# SCHEMATIC_V2.net
KiCad netlist of a schematic drawn in EAGLE
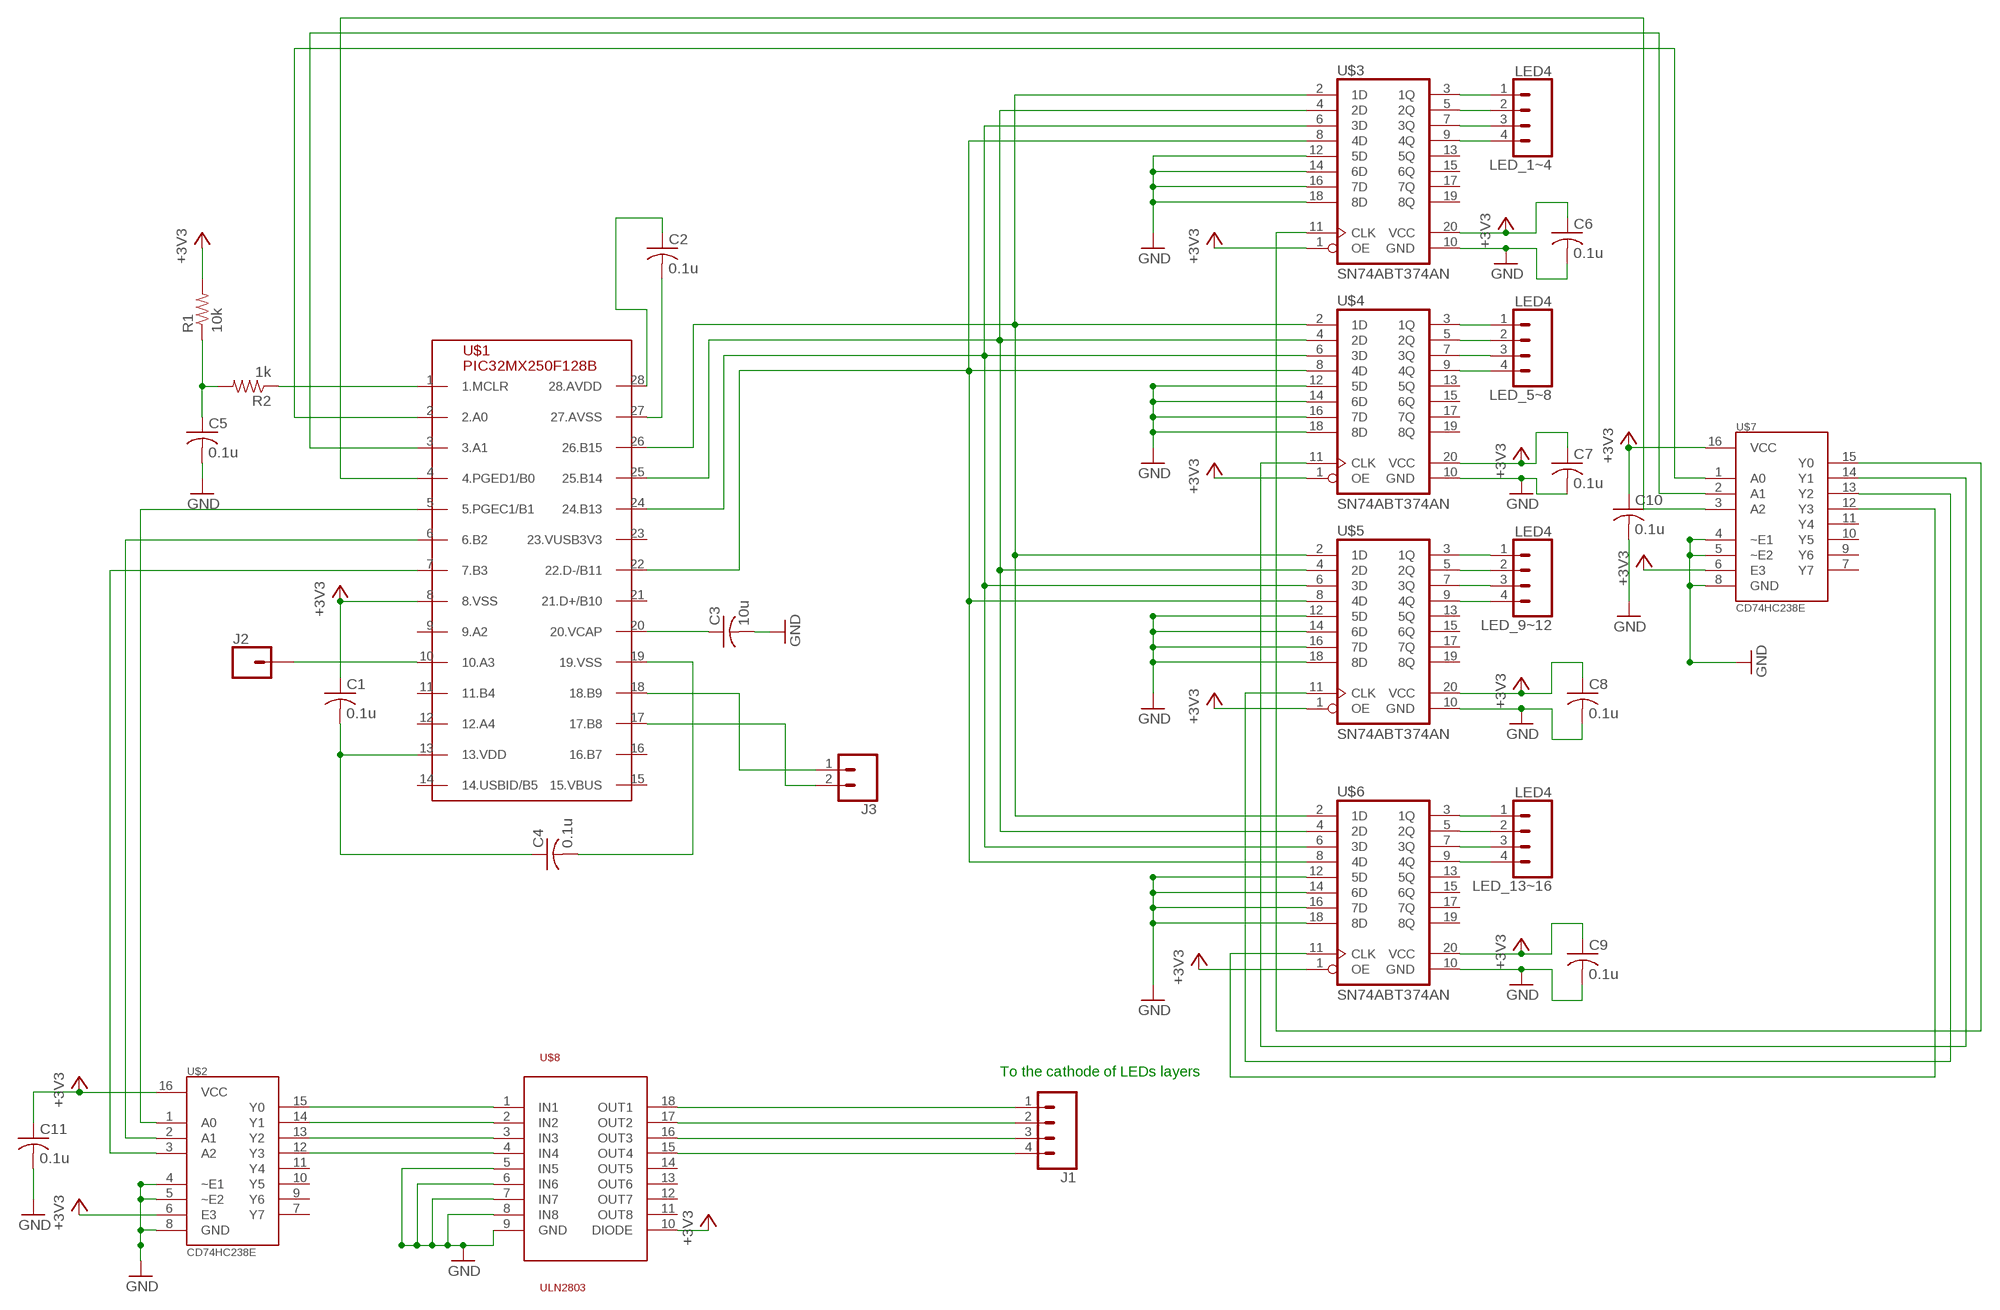
[diagram p0: schematic, sheet 1]

(export (version "E")
  (design (tool "Eeschema 10.0.6"))
  (components
    (comp (ref "C1")
      (value "0.1u")
      (footprint "eagle-import:C025-025X050")
      (libsource (lib "eagle-import") (part "C-US025-025X050"))
    )
    (comp (ref "C2")
      (value "0.1u")
      (footprint "eagle-import:C025-025X050")
      (libsource (lib "eagle-import") (part "C-US025-025X050"))
    )
    (comp (ref "C3")
      (value "10u")
      (footprint "eagle-import:C025-025X050")
      (libsource (lib "eagle-import") (part "C-US025-025X050"))
    )
    (comp (ref "C4")
      (value "0.1u")
      (footprint "eagle-import:C025-025X050")
      (libsource (lib "eagle-import") (part "C-US025-025X050"))
    )
    (comp (ref "C5")
      (value "0.1u")
      (footprint "eagle-import:C025-025X050")
      (libsource (lib "eagle-import") (part "C-US025-025X050"))
    )
    (comp (ref "C6")
      (value "0.1u")
      (footprint "eagle-import:C025-025X050")
      (libsource (lib "eagle-import") (part "C-US025-025X050"))
    )
    (comp (ref "C7")
      (value "0.1u")
      (footprint "eagle-import:C025-025X050")
      (libsource (lib "eagle-import") (part "C-US025-025X050"))
    )
    (comp (ref "C8")
      (value "0.1u")
      (footprint "eagle-import:C025-025X050")
      (libsource (lib "eagle-import") (part "C-US025-025X050"))
    )
    (comp (ref "C9")
      (value "0.1u")
      (footprint "eagle-import:C025-025X050")
      (libsource (lib "eagle-import") (part "C-US025-025X050"))
    )
    (comp (ref "C10")
      (value "0.1u")
      (footprint "eagle-import:C025-025X050")
      (libsource (lib "eagle-import") (part "C-US025-025X050"))
    )
    (comp (ref "C11")
      (value "0.1u")
      (footprint "eagle-import:C025-025X050")
      (libsource (lib "eagle-import") (part "C-US025-025X050"))
    )
    (comp (ref "J1")
      (value "CONN_04")
      (footprint "eagle-import:1X04")
      (libsource (lib "eagle-import") (part "CONN_04"))
    )
    (comp (ref "J2")
      (value "CONN_01")
      (footprint "eagle-import:1X01")
      (libsource (lib "eagle-import") (part "CONN_01"))
    )
    (comp (ref "J3")
      (value "CONN_02")
      (footprint "eagle-import:1X02")
      (libsource (lib "eagle-import") (part "CONN_02"))
    )
    (comp (ref "LED_1~4")
      (value "LED4")
      (footprint "eagle-import:1X04")
      (libsource (lib "eagle-import") (part "LED4"))
    )
    (comp (ref "LED_5~8")
      (value "LED4")
      (footprint "eagle-import:1X04")
      (libsource (lib "eagle-import") (part "LED4"))
    )
    (comp (ref "LED_9~12")
      (value "LED4")
      (footprint "eagle-import:1X04")
      (libsource (lib "eagle-import") (part "LED4"))
    )
    (comp (ref "LED_13~16")
      (value "LED4")
      (footprint "eagle-import:1X04")
      (libsource (lib "eagle-import") (part "LED4"))
    )
    (comp (ref "R1")
      (value "10k")
      (footprint "eagle-import:0204_7")
      (libsource (lib "eagle-import") (part "R-US_0204/7"))
    )
    (comp (ref "R2")
      (value "1k")
      (footprint "eagle-import:0204_7")
      (libsource (lib "eagle-import") (part "R-US_0204/7"))
    )
    (comp (ref "U$1")
      (value "PIC32MX250F128B")
      (footprint "eagle-import:DIL28-3")
      (libsource (lib "eagle-import") (part "PIC32MX250F128B"))
    )
    (comp (ref "U$2")
      (value "CD74HC238E")
      (footprint "eagle-import:DIL16")
      (libsource (lib "eagle-import") (part "CD74HC238E"))
    )
    (comp (ref "U$3")
      (value "SN74ABT374AN")
      (footprint "eagle-import:DIL20")
      (libsource (lib "eagle-import") (part "SN74ABT374AN"))
    )
    (comp (ref "U$4")
      (value "SN74ABT374AN")
      (footprint "eagle-import:DIL20")
      (libsource (lib "eagle-import") (part "SN74ABT374AN"))
    )
    (comp (ref "U$5")
      (value "SN74ABT374AN")
      (footprint "eagle-import:DIL20")
      (libsource (lib "eagle-import") (part "SN74ABT374AN"))
    )
    (comp (ref "U$6")
      (value "SN74ABT374AN")
      (footprint "eagle-import:DIL20")
      (libsource (lib "eagle-import") (part "SN74ABT374AN"))
    )
    (comp (ref "U$7")
      (value "CD74HC238E")
      (footprint "eagle-import:DIL16")
      (libsource (lib "eagle-import") (part "CD74HC238E"))
    )
    (comp (ref "U$8")
      (value "ULN2803")
      (footprint "eagle-import:SO18L")
      (libsource (lib "eagle-import") (part "ULN2803"))
    )
  )
  (nets
    (net (code "1") (name "+3V3") (class "Default")
      (node (ref "C1") (pin "1") (pinfunction "1_1") (pintype "passive"))
      (node (ref "C10") (pin "1") (pinfunction "1_1") (pintype "passive"))
      (node (ref "C11") (pin "1") (pinfunction "1_1") (pintype "passive"))
      (node (ref "C6") (pin "1") (pinfunction "1_1") (pintype "passive"))
      (node (ref "C7") (pin "1") (pinfunction "1_1") (pintype "passive"))
      (node (ref "C8") (pin "1") (pinfunction "1_1") (pintype "passive"))
      (node (ref "C9") (pin "1") (pinfunction "1_1") (pintype "passive"))
      (node (ref "R1") (pin "2") (pinfunction "2_2") (pintype "passive"))
      (node (ref "U$1") (pin "8") (pinfunction "8.VSS_8") (pintype "bidirectional"))
      (node (ref "U$2") (pin "16") (pinfunction "VCC_16") (pintype "bidirectional"))
      (node (ref "U$2") (pin "6") (pinfunction "E3_6") (pintype "bidirectional"))
      (node (ref "U$3") (pin "1") (pinfunction "OE_1") (pintype "input"))
      (node (ref "U$3") (pin "20") (pinfunction "VCC_20") (pintype "bidirectional"))
      (node (ref "U$4") (pin "1") (pinfunction "OE_1") (pintype "input"))
      (node (ref "U$4") (pin "20") (pinfunction "VCC_20") (pintype "bidirectional"))
      (node (ref "U$5") (pin "1") (pinfunction "OE_1") (pintype "input"))
      (node (ref "U$5") (pin "20") (pinfunction "VCC_20") (pintype "bidirectional"))
      (node (ref "U$6") (pin "1") (pinfunction "OE_1") (pintype "input"))
      (node (ref "U$6") (pin "20") (pinfunction "VCC_20") (pintype "bidirectional"))
      (node (ref "U$7") (pin "16") (pinfunction "VCC_16") (pintype "bidirectional"))
      (node (ref "U$7") (pin "6") (pinfunction "E3_6") (pintype "bidirectional"))
      (node (ref "U$8") (pin "10") (pinfunction "DIODE_10") (pintype "power_in"))
    )
    (net (code "2") (name "GND") (class "Default")
      (node (ref "C10") (pin "2") (pinfunction "2_2") (pintype "passive"))
      (node (ref "C11") (pin "2") (pinfunction "2_2") (pintype "passive"))
      (node (ref "C3") (pin "2") (pinfunction "2_2") (pintype "passive"))
      (node (ref "C5") (pin "2") (pinfunction "2_2") (pintype "passive"))
      (node (ref "C6") (pin "2") (pinfunction "2_2") (pintype "passive"))
      (node (ref "C7") (pin "2") (pinfunction "2_2") (pintype "passive"))
      (node (ref "C8") (pin "2") (pinfunction "2_2") (pintype "passive"))
      (node (ref "C9") (pin "2") (pinfunction "2_2") (pintype "passive"))
      (node (ref "U$2") (pin "4") (pinfunction "~{E1}_4") (pintype "bidirectional"))
      (node (ref "U$2") (pin "5") (pinfunction "~{E2}_5") (pintype "bidirectional"))
      (node (ref "U$2") (pin "8") (pinfunction "GND_8") (pintype "bidirectional"))
      (node (ref "U$3") (pin "10") (pinfunction "GND_10") (pintype "bidirectional"))
      (node (ref "U$3") (pin "12") (pinfunction "5D_12") (pintype "input"))
      (node (ref "U$3") (pin "14") (pinfunction "6D_14") (pintype "input"))
      (node (ref "U$3") (pin "16") (pinfunction "7D_16") (pintype "input"))
      (node (ref "U$3") (pin "18") (pinfunction "8D_18") (pintype "input"))
      (node (ref "U$4") (pin "10") (pinfunction "GND_10") (pintype "bidirectional"))
      (node (ref "U$4") (pin "12") (pinfunction "5D_12") (pintype "input"))
      (node (ref "U$4") (pin "14") (pinfunction "6D_14") (pintype "input"))
      (node (ref "U$4") (pin "16") (pinfunction "7D_16") (pintype "input"))
      (node (ref "U$4") (pin "18") (pinfunction "8D_18") (pintype "input"))
      (node (ref "U$5") (pin "10") (pinfunction "GND_10") (pintype "bidirectional"))
      (node (ref "U$5") (pin "12") (pinfunction "5D_12") (pintype "input"))
      (node (ref "U$5") (pin "14") (pinfunction "6D_14") (pintype "input"))
      (node (ref "U$5") (pin "16") (pinfunction "7D_16") (pintype "input"))
      (node (ref "U$5") (pin "18") (pinfunction "8D_18") (pintype "input"))
      (node (ref "U$6") (pin "10") (pinfunction "GND_10") (pintype "bidirectional"))
      (node (ref "U$6") (pin "12") (pinfunction "5D_12") (pintype "input"))
      (node (ref "U$6") (pin "14") (pinfunction "6D_14") (pintype "input"))
      (node (ref "U$6") (pin "16") (pinfunction "7D_16") (pintype "input"))
      (node (ref "U$6") (pin "18") (pinfunction "8D_18") (pintype "input"))
      (node (ref "U$7") (pin "4") (pinfunction "~{E1}_4") (pintype "bidirectional"))
      (node (ref "U$7") (pin "5") (pinfunction "~{E2}_5") (pintype "bidirectional"))
      (node (ref "U$7") (pin "8") (pinfunction "GND_8") (pintype "bidirectional"))
      (node (ref "U$8") (pin "5") (pinfunction "IN5_5") (pintype "input"))
      (node (ref "U$8") (pin "6") (pinfunction "IN6_6") (pintype "input"))
      (node (ref "U$8") (pin "7") (pinfunction "IN7_7") (pintype "input"))
      (node (ref "U$8") (pin "8") (pinfunction "IN8_8") (pintype "input"))
      (node (ref "U$8") (pin "9") (pinfunction "GND_9") (pintype "power_in"))
    )
    (net (code "3") (name "Net-(C5-Pad1)") (class "Default")
      (node (ref "C5") (pin "1") (pinfunction "1_1") (pintype "passive"))
      (node (ref "R1") (pin "1") (pinfunction "1_1") (pintype "passive"))
      (node (ref "R2") (pin "2") (pinfunction "2_2") (pintype "passive"))
    )
    (net (code "4") (name "Net-(U$1-1.MCLR)") (class "Default")
      (node (ref "R2") (pin "1") (pinfunction "1_1") (pintype "passive"))
      (node (ref "U$1") (pin "1") (pinfunction "1.MCLR_1") (pintype "bidirectional"))
    )
    (net (code "5") (name "Net-(U$1-2.A0)") (class "Default")
      (node (ref "U$1") (pin "2") (pinfunction "2.A0_2") (pintype "bidirectional"))
      (node (ref "U$7") (pin "1") (pinfunction "A0_1") (pintype "bidirectional"))
    )
    (net (code "6") (name "Net-(U$1-3.A1)") (class "Default")
      (node (ref "U$1") (pin "3") (pinfunction "3.A1_3") (pintype "bidirectional"))
      (node (ref "U$7") (pin "2") (pinfunction "A1_2") (pintype "bidirectional"))
    )
    (net (code "7") (name "Net-(U$1-4.PGED1{slash}B0)") (class "Default")
      (node (ref "U$1") (pin "4") (pinfunction "4.PGED1/B0_4") (pintype "bidirectional"))
      (node (ref "U$7") (pin "3") (pinfunction "A2_3") (pintype "bidirectional"))
    )
    (net (code "8") (name "Net-(U$1-5.PGEC1{slash}B1)") (class "Default")
      (node (ref "U$1") (pin "5") (pinfunction "5.PGEC1/B1_5") (pintype "bidirectional"))
      (node (ref "U$2") (pin "1") (pinfunction "A0_1") (pintype "bidirectional"))
    )
    (net (code "9") (name "Net-(U$1-6.B2)") (class "Default")
      (node (ref "U$1") (pin "6") (pinfunction "6.B2_6") (pintype "bidirectional"))
      (node (ref "U$2") (pin "2") (pinfunction "A1_2") (pintype "bidirectional"))
    )
    (net (code "10") (name "Net-(U$1-7.B3)") (class "Default")
      (node (ref "U$1") (pin "7") (pinfunction "7.B3_7") (pintype "bidirectional"))
      (node (ref "U$2") (pin "3") (pinfunction "A2_3") (pintype "bidirectional"))
    )
    (net (code "11") (name "Net-(U$1-10.A3)") (class "Default")
      (node (ref "J2") (pin "1") (pinfunction "1_1") (pintype "passive"))
      (node (ref "U$1") (pin "10") (pinfunction "10.A3_10") (pintype "bidirectional"))
    )
    (net (code "12") (name "Net-(U$1-13.VDD)") (class "Default")
      (node (ref "C1") (pin "2") (pinfunction "2_2") (pintype "passive"))
      (node (ref "C4") (pin "1") (pinfunction "1_1") (pintype "passive"))
      (node (ref "U$1") (pin "13") (pinfunction "13.VDD_13") (pintype "bidirectional"))
    )
    (net (code "13") (name "Net-(U$1-17.B8)") (class "Default")
      (node (ref "J3") (pin "2") (pinfunction "2_2") (pintype "passive"))
      (node (ref "U$1") (pin "17") (pinfunction "17.B8_17") (pintype "bidirectional"))
    )
    (net (code "14") (name "Net-(U$1-18.B9)") (class "Default")
      (node (ref "J3") (pin "1") (pinfunction "1_1") (pintype "passive"))
      (node (ref "U$1") (pin "18") (pinfunction "18.B9_18") (pintype "bidirectional"))
    )
    (net (code "15") (name "Net-(U$1-19.VSS)") (class "Default")
      (node (ref "C4") (pin "2") (pinfunction "2_2") (pintype "passive"))
      (node (ref "U$1") (pin "19") (pinfunction "19.VSS_19") (pintype "bidirectional"))
    )
    (net (code "16") (name "Net-(U$1-20.VCAP)") (class "Default")
      (node (ref "C3") (pin "1") (pinfunction "1_1") (pintype "passive"))
      (node (ref "U$1") (pin "20") (pinfunction "20.VCAP_20") (pintype "bidirectional"))
    )
    (net (code "17") (name "Net-(U$1-22.D-{slash}B11)") (class "Default")
      (node (ref "U$1") (pin "22") (pinfunction "22.D-/B11_22") (pintype "bidirectional"))
      (node (ref "U$3") (pin "8") (pinfunction "4D_8") (pintype "input"))
      (node (ref "U$4") (pin "8") (pinfunction "4D_8") (pintype "input"))
      (node (ref "U$5") (pin "8") (pinfunction "4D_8") (pintype "input"))
      (node (ref "U$6") (pin "8") (pinfunction "4D_8") (pintype "input"))
    )
    (net (code "18") (name "Net-(U$1-24.B13)") (class "Default")
      (node (ref "U$1") (pin "24") (pinfunction "24.B13_24") (pintype "bidirectional"))
      (node (ref "U$3") (pin "6") (pinfunction "3D_6") (pintype "input"))
      (node (ref "U$4") (pin "6") (pinfunction "3D_6") (pintype "input"))
      (node (ref "U$5") (pin "6") (pinfunction "3D_6") (pintype "input"))
      (node (ref "U$6") (pin "6") (pinfunction "3D_6") (pintype "input"))
    )
    (net (code "19") (name "Net-(U$1-25.B14)") (class "Default")
      (node (ref "U$1") (pin "25") (pinfunction "25.B14_25") (pintype "bidirectional"))
      (node (ref "U$3") (pin "4") (pinfunction "2D_4") (pintype "input"))
      (node (ref "U$4") (pin "4") (pinfunction "2D_4") (pintype "input"))
      (node (ref "U$5") (pin "4") (pinfunction "2D_4") (pintype "input"))
      (node (ref "U$6") (pin "4") (pinfunction "2D_4") (pintype "input"))
    )
    (net (code "20") (name "Net-(U$1-26.B15)") (class "Default")
      (node (ref "U$1") (pin "26") (pinfunction "26.B15_26") (pintype "bidirectional"))
      (node (ref "U$3") (pin "2") (pinfunction "1D_2") (pintype "input"))
      (node (ref "U$4") (pin "2") (pinfunction "1D_2") (pintype "input"))
      (node (ref "U$5") (pin "2") (pinfunction "1D_2") (pintype "input"))
      (node (ref "U$6") (pin "2") (pinfunction "1D_2") (pintype "input"))
    )
    (net (code "21") (name "Net-(U$1-27.AVSS)") (class "Default")
      (node (ref "C2") (pin "2") (pinfunction "2_2") (pintype "passive"))
      (node (ref "U$1") (pin "27") (pinfunction "27.AVSS_27") (pintype "bidirectional"))
    )
    (net (code "22") (name "Net-(U$1-28.AVDD)") (class "Default")
      (node (ref "C2") (pin "1") (pinfunction "1_1") (pintype "passive"))
      (node (ref "U$1") (pin "28") (pinfunction "28.AVDD_28") (pintype "bidirectional"))
    )
    (net (code "23") (name "Net-(U$2-Y0)") (class "Default")
      (node (ref "U$2") (pin "15") (pinfunction "Y0_15") (pintype "bidirectional"))
      (node (ref "U$8") (pin "1") (pinfunction "IN1_1") (pintype "input"))
    )
    (net (code "24") (name "Net-(U$2-Y1)") (class "Default")
      (node (ref "U$2") (pin "14") (pinfunction "Y1_14") (pintype "bidirectional"))
      (node (ref "U$8") (pin "2") (pinfunction "IN2_2") (pintype "input"))
    )
    (net (code "25") (name "Net-(U$2-Y2)") (class "Default")
      (node (ref "U$2") (pin "13") (pinfunction "Y2_13") (pintype "bidirectional"))
      (node (ref "U$8") (pin "3") (pinfunction "IN3_3") (pintype "input"))
    )
    (net (code "26") (name "Net-(U$2-Y3)") (class "Default")
      (node (ref "U$2") (pin "12") (pinfunction "Y3_12") (pintype "bidirectional"))
      (node (ref "U$8") (pin "4") (pinfunction "IN4_4") (pintype "input"))
    )
    (net (code "27") (name "Net-(U$3-1Q)") (class "Default")
      (node (ref "LED_1~4") (pin "1") (pinfunction "1_1") (pintype "passive"))
      (node (ref "U$3") (pin "3") (pinfunction "1Q_3") (pintype "tri_state"))
    )
    (net (code "28") (name "Net-(U$3-2Q)") (class "Default")
      (node (ref "LED_1~4") (pin "2") (pinfunction "2_2") (pintype "passive"))
      (node (ref "U$3") (pin "5") (pinfunction "2Q_5") (pintype "tri_state"))
    )
    (net (code "29") (name "Net-(U$3-3Q)") (class "Default")
      (node (ref "LED_1~4") (pin "3") (pinfunction "3_3") (pintype "passive"))
      (node (ref "U$3") (pin "7") (pinfunction "3Q_7") (pintype "tri_state"))
    )
    (net (code "30") (name "Net-(U$3-4Q)") (class "Default")
      (node (ref "LED_1~4") (pin "4") (pinfunction "4_4") (pintype "passive"))
      (node (ref "U$3") (pin "9") (pinfunction "4Q_9") (pintype "tri_state"))
    )
    (net (code "31") (name "Net-(U$3-CLK)") (class "Default")
      (node (ref "U$3") (pin "11") (pinfunction "CLK_11") (pintype "input"))
      (node (ref "U$7") (pin "15") (pinfunction "Y0_15") (pintype "bidirectional"))
    )
    (net (code "32") (name "Net-(U$4-1Q)") (class "Default")
      (node (ref "LED_5~8") (pin "1") (pinfunction "1_1") (pintype "passive"))
      (node (ref "U$4") (pin "3") (pinfunction "1Q_3") (pintype "tri_state"))
    )
    (net (code "33") (name "Net-(U$4-2Q)") (class "Default")
      (node (ref "LED_5~8") (pin "2") (pinfunction "2_2") (pintype "passive"))
      (node (ref "U$4") (pin "5") (pinfunction "2Q_5") (pintype "tri_state"))
    )
    (net (code "34") (name "Net-(U$4-3Q)") (class "Default")
      (node (ref "LED_5~8") (pin "3") (pinfunction "3_3") (pintype "passive"))
      (node (ref "U$4") (pin "7") (pinfunction "3Q_7") (pintype "tri_state"))
    )
    (net (code "35") (name "Net-(U$4-4Q)") (class "Default")
      (node (ref "LED_5~8") (pin "4") (pinfunction "4_4") (pintype "passive"))
      (node (ref "U$4") (pin "9") (pinfunction "4Q_9") (pintype "tri_state"))
    )
    (net (code "36") (name "Net-(U$4-CLK)") (class "Default")
      (node (ref "U$4") (pin "11") (pinfunction "CLK_11") (pintype "input"))
      (node (ref "U$7") (pin "14") (pinfunction "Y1_14") (pintype "bidirectional"))
    )
    (net (code "37") (name "Net-(U$5-1Q)") (class "Default")
      (node (ref "LED_9~12") (pin "1") (pinfunction "1_1") (pintype "passive"))
      (node (ref "U$5") (pin "3") (pinfunction "1Q_3") (pintype "tri_state"))
    )
    (net (code "38") (name "Net-(U$5-2Q)") (class "Default")
      (node (ref "LED_9~12") (pin "2") (pinfunction "2_2") (pintype "passive"))
      (node (ref "U$5") (pin "5") (pinfunction "2Q_5") (pintype "tri_state"))
    )
    (net (code "39") (name "Net-(U$5-3Q)") (class "Default")
      (node (ref "LED_9~12") (pin "3") (pinfunction "3_3") (pintype "passive"))
      (node (ref "U$5") (pin "7") (pinfunction "3Q_7") (pintype "tri_state"))
    )
    (net (code "40") (name "Net-(U$5-4Q)") (class "Default")
      (node (ref "LED_9~12") (pin "4") (pinfunction "4_4") (pintype "passive"))
      (node (ref "U$5") (pin "9") (pinfunction "4Q_9") (pintype "tri_state"))
    )
    (net (code "41") (name "Net-(U$5-CLK)") (class "Default")
      (node (ref "U$5") (pin "11") (pinfunction "CLK_11") (pintype "input"))
      (node (ref "U$7") (pin "13") (pinfunction "Y2_13") (pintype "bidirectional"))
    )
    (net (code "42") (name "Net-(U$6-1Q)") (class "Default")
      (node (ref "LED_13~16") (pin "1") (pinfunction "1_1") (pintype "passive"))
      (node (ref "U$6") (pin "3") (pinfunction "1Q_3") (pintype "tri_state"))
    )
    (net (code "43") (name "Net-(U$6-2Q)") (class "Default")
      (node (ref "LED_13~16") (pin "2") (pinfunction "2_2") (pintype "passive"))
      (node (ref "U$6") (pin "5") (pinfunction "2Q_5") (pintype "tri_state"))
    )
    (net (code "44") (name "Net-(U$6-3Q)") (class "Default")
      (node (ref "LED_13~16") (pin "3") (pinfunction "3_3") (pintype "passive"))
      (node (ref "U$6") (pin "7") (pinfunction "3Q_7") (pintype "tri_state"))
    )
    (net (code "45") (name "Net-(U$6-4Q)") (class "Default")
      (node (ref "LED_13~16") (pin "4") (pinfunction "4_4") (pintype "passive"))
      (node (ref "U$6") (pin "9") (pinfunction "4Q_9") (pintype "tri_state"))
    )
    (net (code "46") (name "Net-(U$6-CLK)") (class "Default")
      (node (ref "U$6") (pin "11") (pinfunction "CLK_11") (pintype "input"))
      (node (ref "U$7") (pin "12") (pinfunction "Y3_12") (pintype "bidirectional"))
    )
    (net (code "47") (name "Net-(U$8-OUT1)") (class "Default")
      (node (ref "J1") (pin "1") (pinfunction "1_1") (pintype "passive"))
      (node (ref "U$8") (pin "18") (pinfunction "OUT1_18") (pintype "open_collector"))
    )
    (net (code "48") (name "Net-(U$8-OUT2)") (class "Default")
      (node (ref "J1") (pin "2") (pinfunction "2_2") (pintype "passive"))
      (node (ref "U$8") (pin "17") (pinfunction "OUT2_17") (pintype "open_collector"))
    )
    (net (code "49") (name "Net-(U$8-OUT3)") (class "Default")
      (node (ref "J1") (pin "3") (pinfunction "3_3") (pintype "passive"))
      (node (ref "U$8") (pin "16") (pinfunction "OUT3_16") (pintype "open_collector"))
    )
    (net (code "50") (name "Net-(U$8-OUT4)") (class "Default")
      (node (ref "J1") (pin "4") (pinfunction "4_4") (pintype "passive"))
      (node (ref "U$8") (pin "15") (pinfunction "OUT4_15") (pintype "open_collector"))
    )
    (net (code "51") (name "unconnected-(U$1-9.A2-Pad9)") (class "Default")
      (node (ref "U$1") (pin "9") (pinfunction "9.A2_9") (pintype "bidirectional"))
    )
    (net (code "52") (name "unconnected-(U$1-11.B4-Pad11)") (class "Default")
      (node (ref "U$1") (pin "11") (pinfunction "11.B4_11") (pintype "bidirectional"))
    )
    (net (code "53") (name "unconnected-(U$1-12.A4-Pad12)") (class "Default")
      (node (ref "U$1") (pin "12") (pinfunction "12.A4_12") (pintype "bidirectional"))
    )
    (net (code "54") (name "unconnected-(U$1-14.USBID{slash}B5-Pad14)") (class "Default")
      (node (ref "U$1") (pin "14") (pinfunction "14.USBID/B5_14") (pintype "bidirectional"))
    )
    (net (code "55") (name "unconnected-(U$1-15.VBUS-Pad15)") (class "Default")
      (node (ref "U$1") (pin "15") (pinfunction "15.VBUS_15") (pintype "bidirectional"))
    )
    (net (code "56") (name "unconnected-(U$1-16.B7-Pad16)") (class "Default")
      (node (ref "U$1") (pin "16") (pinfunction "16.B7_16") (pintype "bidirectional"))
    )
    (net (code "57") (name "unconnected-(U$1-21.D+{slash}B10-Pad21)") (class "Default")
      (node (ref "U$1") (pin "21") (pinfunction "21.D+/B10_21") (pintype "bidirectional"))
    )
    (net (code "58") (name "unconnected-(U$1-23.VUSB3V3-Pad23)") (class "Default")
      (node (ref "U$1") (pin "23") (pinfunction "23.VUSB3V3_23") (pintype "bidirectional"))
    )
    (net (code "59") (name "unconnected-(U$2-Y4-Pad11)") (class "Default")
      (node (ref "U$2") (pin "11") (pinfunction "Y4_11") (pintype "bidirectional"))
    )
    (net (code "60") (name "unconnected-(U$2-Y5-Pad10)") (class "Default")
      (node (ref "U$2") (pin "10") (pinfunction "Y5_10") (pintype "bidirectional"))
    )
    (net (code "61") (name "unconnected-(U$2-Y6-Pad9)") (class "Default")
      (node (ref "U$2") (pin "9") (pinfunction "Y6_9") (pintype "bidirectional"))
    )
    (net (code "62") (name "unconnected-(U$2-Y7-Pad7)") (class "Default")
      (node (ref "U$2") (pin "7") (pinfunction "Y7_7") (pintype "bidirectional"))
    )
    (net (code "63") (name "unconnected-(U$3-5Q-Pad13)") (class "Default")
      (node (ref "U$3") (pin "13") (pinfunction "5Q_13") (pintype "tri_state"))
    )
    (net (code "64") (name "unconnected-(U$3-6Q-Pad15)") (class "Default")
      (node (ref "U$3") (pin "15") (pinfunction "6Q_15") (pintype "tri_state"))
    )
    (net (code "65") (name "unconnected-(U$3-7Q-Pad17)") (class "Default")
      (node (ref "U$3") (pin "17") (pinfunction "7Q_17") (pintype "tri_state"))
    )
    (net (code "66") (name "unconnected-(U$3-8Q-Pad19)") (class "Default")
      (node (ref "U$3") (pin "19") (pinfunction "8Q_19") (pintype "tri_state"))
    )
    (net (code "67") (name "unconnected-(U$4-5Q-Pad13)") (class "Default")
      (node (ref "U$4") (pin "13") (pinfunction "5Q_13") (pintype "tri_state"))
    )
    (net (code "68") (name "unconnected-(U$4-6Q-Pad15)") (class "Default")
      (node (ref "U$4") (pin "15") (pinfunction "6Q_15") (pintype "tri_state"))
    )
    (net (code "69") (name "unconnected-(U$4-7Q-Pad17)") (class "Default")
      (node (ref "U$4") (pin "17") (pinfunction "7Q_17") (pintype "tri_state"))
    )
    (net (code "70") (name "unconnected-(U$4-8Q-Pad19)") (class "Default")
      (node (ref "U$4") (pin "19") (pinfunction "8Q_19") (pintype "tri_state"))
    )
    (net (code "71") (name "unconnected-(U$5-5Q-Pad13)") (class "Default")
      (node (ref "U$5") (pin "13") (pinfunction "5Q_13") (pintype "tri_state"))
    )
    (net (code "72") (name "unconnected-(U$5-6Q-Pad15)") (class "Default")
      (node (ref "U$5") (pin "15") (pinfunction "6Q_15") (pintype "tri_state"))
    )
    (net (code "73") (name "unconnected-(U$5-7Q-Pad17)") (class "Default")
      (node (ref "U$5") (pin "17") (pinfunction "7Q_17") (pintype "tri_state"))
    )
    (net (code "74") (name "unconnected-(U$5-8Q-Pad19)") (class "Default")
      (node (ref "U$5") (pin "19") (pinfunction "8Q_19") (pintype "tri_state"))
    )
    (net (code "75") (name "unconnected-(U$6-5Q-Pad13)") (class "Default")
      (node (ref "U$6") (pin "13") (pinfunction "5Q_13") (pintype "tri_state"))
    )
    (net (code "76") (name "unconnected-(U$6-6Q-Pad15)") (class "Default")
      (node (ref "U$6") (pin "15") (pinfunction "6Q_15") (pintype "tri_state"))
    )
    (net (code "77") (name "unconnected-(U$6-7Q-Pad17)") (class "Default")
      (node (ref "U$6") (pin "17") (pinfunction "7Q_17") (pintype "tri_state"))
    )
    (net (code "78") (name "unconnected-(U$6-8Q-Pad19)") (class "Default")
      (node (ref "U$6") (pin "19") (pinfunction "8Q_19") (pintype "tri_state"))
    )
    (net (code "79") (name "unconnected-(U$7-Y4-Pad11)") (class "Default")
      (node (ref "U$7") (pin "11") (pinfunction "Y4_11") (pintype "bidirectional"))
    )
    (net (code "80") (name "unconnected-(U$7-Y5-Pad10)") (class "Default")
      (node (ref "U$7") (pin "10") (pinfunction "Y5_10") (pintype "bidirectional"))
    )
    (net (code "81") (name "unconnected-(U$7-Y6-Pad9)") (class "Default")
      (node (ref "U$7") (pin "9") (pinfunction "Y6_9") (pintype "bidirectional"))
    )
    (net (code "82") (name "unconnected-(U$7-Y7-Pad7)") (class "Default")
      (node (ref "U$7") (pin "7") (pinfunction "Y7_7") (pintype "bidirectional"))
    )
    (net (code "83") (name "unconnected-(U$8-OUT5-Pad14)") (class "Default")
      (node (ref "U$8") (pin "14") (pinfunction "OUT5_14") (pintype "open_collector"))
    )
    (net (code "84") (name "unconnected-(U$8-OUT6-Pad13)") (class "Default")
      (node (ref "U$8") (pin "13") (pinfunction "OUT6_13") (pintype "open_collector"))
    )
    (net (code "85") (name "unconnected-(U$8-OUT7-Pad12)") (class "Default")
      (node (ref "U$8") (pin "12") (pinfunction "OUT7_12") (pintype "open_collector"))
    )
    (net (code "86") (name "unconnected-(U$8-OUT8-Pad11)") (class "Default")
      (node (ref "U$8") (pin "11") (pinfunction "OUT8_11") (pintype "open_collector"))
    )
  )
)
